# Sheet1.net
KiCad netlist of a schematic drawn in Altium Designer
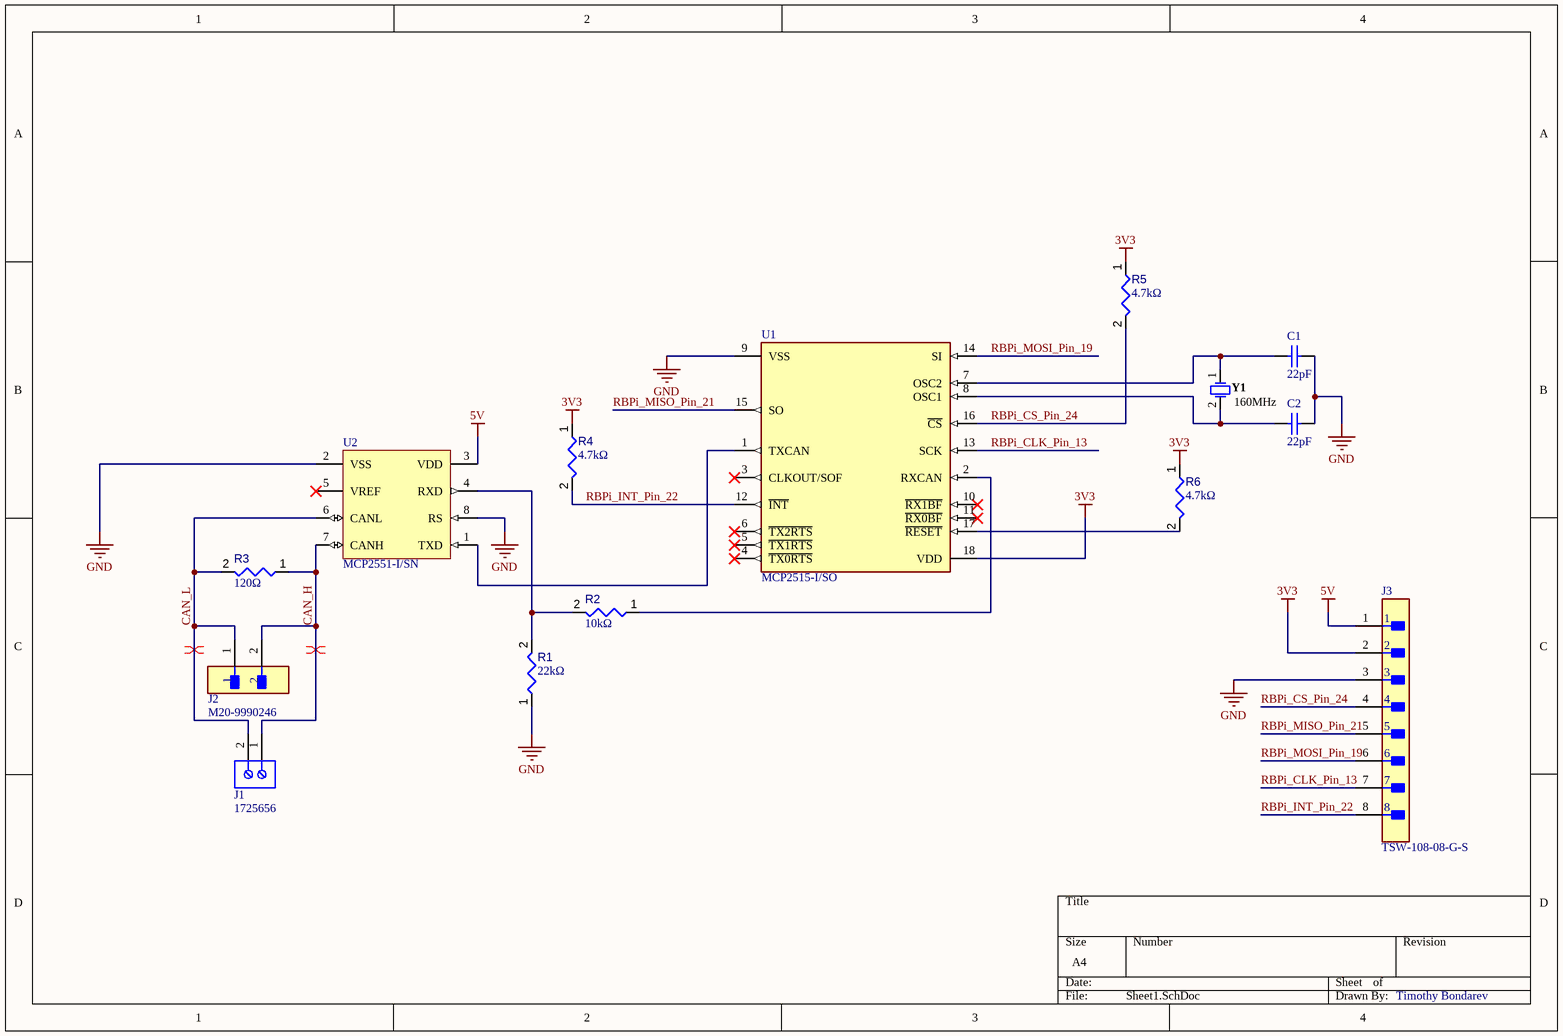
[diagram p0: Sheet1.SchDoc]

(export (version "E")
  (design (tool "Eeschema 10.0.6"))
  (components
    (comp (ref "C1")
      (value "22pF")
      (footprint "CAPC2013X140X50LL20T25")
      (description "Chip Capacitor, 2.2 uF, +/- 10%, 10 V, -55 to 85 degC, 0805 (2012 Metric), RoHS, Tape and Reel")
      (fields (field (name "MANUFACTURER") "AVX"))
      (libsource (lib "Altium Content Vault") (part "CAP-NP-2"))
    )
    (comp (ref "C2")
      (value "22pF")
      (footprint "CAPC2013X140X50LL20T25")
      (description "Chip Capacitor, 2.2 uF, +/- 10%, 10 V, -55 to 85 degC, 0805 (2012 Metric), RoHS, Tape and Reel")
      (fields (field (name "MANUFACTURER") "AVX"))
      (libsource (lib "Altium Content Vault") (part "CAP-NP-2"))
    )
    (comp (ref "J1")
      (value "1725656")
      (footprint "PHOE-1725656-2")
      (description "Male Header, Pitch 2.54 mm, 1 x 2 Position, Height 9 mm, Tail Length 3.5 mm")
      (fields (field (name "MANUFACTURER") "Phoenix Contact"))
      (libsource (lib "Altium Content Vault") (part "CN-1P-F-TB2"))
    )
    (comp (ref "J2")
      (value "M20-9990246")
      (footprint "FP-M20-9990246-MFG")
      (description "CONN HEADER VERT 2POS 2.54MM")
      (fields
        (field (name "OCTOPART") "https://octopart.com/m20-9990246-harwin-2590635")
        (field (name "MANUFACTURER") "Harwin")
      )
      (libsource (lib "Altium Content Vault") (part "3bc925449376181038e59eaffc5286c"))
    )
    (comp (ref "J3")
      (value "TSW-108-08-G-S")
      (footprint "FP-TSW-108-08-G-S-MFG")
      (description "CONN HEADER VERT 8POS 2.54MM")
      (fields
        (field (name "MANUFACTURER") "Samtec")
        (field (name "OCTOPART") "https://octopart.com/tsw-108-08-g-s-samtec-272653")
      )
      (libsource (lib "Altium Content Vault") (part "99ec2b232beb5d2356d4d77f6a047f0"))
    )
    (comp (ref "R1")
      (value "22kΩ")
      (footprint "RESC0805(2012)_L")
      (description "1K 0.125W 5% 0805 (2012 Metric)  SMD")
      (fields (field (name "POWER") "0.125W") (field (name "TOLERANCE") "5%"))
      (libsource (lib "Relectric Car Team") (part "1KR5J"))
    )
    (comp (ref "R2")
      (value "10kΩ")
      (footprint "RESC0805(2012)_L")
      (description "1K 0.125W 5% 0805 (2012 Metric)  SMD")
      (fields (field (name "POWER") "0.125W") (field (name "TOLERANCE") "5%"))
      (libsource (lib "Relectric Car Team") (part "1KR5J"))
    )
    (comp (ref "R3")
      (value "120Ω")
      (footprint "RESC0805(2012)_L")
      (description "1K 0.125W 5% 0805 (2012 Metric)  SMD")
      (fields (field (name "POWER") "0.125W") (field (name "TOLERANCE") "5%"))
      (libsource (lib "Relectric Car Team") (part "1KR5J"))
    )
    (comp (ref "R4")
      (value "4.7kΩ")
      (footprint "RESC0805(2012)_L")
      (description "1K 0.125W 5% 0805 (2012 Metric)  SMD")
      (fields (field (name "POWER") "0.125W") (field (name "TOLERANCE") "5%"))
      (libsource (lib "Relectric Car Team") (part "1KR5J"))
    )
    (comp (ref "R5")
      (value "4.7kΩ")
      (footprint "RESC0805(2012)_L")
      (description "1K 0.125W 5% 0805 (2012 Metric)  SMD")
      (fields (field (name "POWER") "0.125W") (field (name "TOLERANCE") "5%"))
      (libsource (lib "Relectric Car Team") (part "1KR5J"))
    )
    (comp (ref "R6")
      (value "4.7kΩ")
      (footprint "RESC0805(2012)_L")
      (description "1K 0.125W 5% 0805 (2012 Metric)  SMD")
      (fields (field (name "POWER") "0.125W") (field (name "TOLERANCE") "5%"))
      (libsource (lib "Relectric Car Team") (part "1KR5J"))
    )
    (comp (ref "U1")
      (value "MCP2515-I/SO")
      (footprint "FP-C04-051-MFG")
      (description "IC CAN CONTROLLER W/SPI 18SOIC")
      (fields
        (field (name "MANUFACTURER") "Microchip")
        (field (name "OCTOPART") "https://octopart.com/mcp2515-i%2Fso-microchip-430187")
      )
      (libsource (lib "Altium Content Vault") (part "1c78ea6ff576bac94664e2637e1b479"))
    )
    (comp (ref "U2")
      (value "MCP2551-I/SN")
      (footprint "MCHP-SN8_V")
      (fields (field (name "MANUFACTURER") "Microchip"))
      (libsource (lib "Altium Content Vault") (part "MCHP-MCP2551-SN8"))
    )
    (comp (ref "Y1")
      (value "160MHz")
      (footprint "FOX-FOXSLF-2_V")
      (description "Resistance Weld Thru-Hole Crystal, 12 MHz, +/-30 ppm, -20 to 70 degC, 2-Pin THD, RoHS, Bulk")
      (libsource (lib "Altium Content Vault") (part "XTAL-1-2-2"))
    )
  )
  (nets
    (net (code "1") (name "/CAN_H") (class "Default")
      (node (ref "J1") (pin "1") (pinfunction "1_1") (pintype "passive"))
      (node (ref "J2") (pin "2") (pinfunction "2_2") (pintype "passive"))
      (node (ref "R3") (pin "1") (pinfunction "1_1") (pintype "passive"))
      (node (ref "U2") (pin "7") (pinfunction "CANH_7") (pintype "bidirectional"))
    )
    (net (code "2") (name "/CAN_L") (class "Default")
      (node (ref "J1") (pin "2") (pinfunction "2_2") (pintype "passive"))
      (node (ref "J2") (pin "1") (pinfunction "1_1") (pintype "passive"))
      (node (ref "R3") (pin "2") (pinfunction "2_2") (pintype "passive"))
      (node (ref "U2") (pin "6") (pinfunction "CANL_6") (pintype "bidirectional"))
    )
    (net (code "3") (name "/RBPi_CLK_Pin_13") (class "Default")
      (node (ref "J3") (pin "7") (pinfunction "7_7") (pintype "passive"))
      (node (ref "U1") (pin "13") (pinfunction "SCK_13") (pintype "input"))
    )
    (net (code "4") (name "/RBPi_CS_Pin_24") (class "Default")
      (node (ref "J3") (pin "4") (pinfunction "4_4") (pintype "passive"))
      (node (ref "R5") (pin "2") (pinfunction "2_2") (pintype "passive"))
      (node (ref "U1") (pin "16") (pinfunction "~{CS}_16") (pintype "input"))
    )
    (net (code "5") (name "/RBPi_INT_Pin_22") (class "Default")
      (node (ref "J3") (pin "8") (pinfunction "8_8") (pintype "passive"))
      (node (ref "R4") (pin "2") (pinfunction "2_2") (pintype "passive"))
      (node (ref "U1") (pin "12") (pinfunction "~{INT}_12") (pintype "output"))
    )
    (net (code "6") (name "/RBPi_MISO_Pin_21") (class "Default")
      (node (ref "J3") (pin "5") (pinfunction "5_5") (pintype "passive"))
      (node (ref "U1") (pin "15") (pinfunction "SO_15") (pintype "output"))
    )
    (net (code "7") (name "/RBPi_MOSI_Pin_19") (class "Default")
      (node (ref "J3") (pin "6") (pinfunction "6_6") (pintype "passive"))
      (node (ref "U1") (pin "14") (pinfunction "SI_14") (pintype "input"))
    )
    (net (code "8") (name "3V3") (class "Default")
      (node (ref "J3") (pin "2") (pinfunction "2_2") (pintype "passive"))
      (node (ref "R4") (pin "1") (pinfunction "1_1") (pintype "passive"))
      (node (ref "R5") (pin "1") (pinfunction "1_1") (pintype "passive"))
      (node (ref "R6") (pin "1") (pinfunction "1_1") (pintype "passive"))
      (node (ref "U1") (pin "18") (pinfunction "VDD_18") (pintype "power_in"))
    )
    (net (code "9") (name "5V") (class "Default")
      (node (ref "J3") (pin "1") (pinfunction "1_1") (pintype "passive"))
      (node (ref "U2") (pin "3") (pinfunction "VDD_3") (pintype "power_in"))
    )
    (net (code "10") (name "GND") (class "Default")
      (node (ref "C1") (pin "1") (pinfunction "1_1") (pintype "passive"))
      (node (ref "C2") (pin "1") (pinfunction "1_1") (pintype "passive"))
      (node (ref "J3") (pin "3") (pinfunction "3_3") (pintype "passive"))
      (node (ref "R1") (pin "1") (pinfunction "1_1") (pintype "passive"))
      (node (ref "U1") (pin "9") (pinfunction "VSS_9") (pintype "power_in"))
      (node (ref "U2") (pin "2") (pinfunction "VSS_2") (pintype "power_in"))
      (node (ref "U2") (pin "8") (pinfunction "RS_8") (pintype "input"))
    )
    (net (code "11") (name "Net-(U1-OSC1)") (class "Default")
      (node (ref "C2") (pin "2") (pinfunction "2_2") (pintype "passive"))
      (node (ref "U1") (pin "8") (pinfunction "OSC1_8") (pintype "input"))
      (node (ref "Y1") (pin "2") (pinfunction "2_2") (pintype "passive"))
    )
    (net (code "12") (name "Net-(U1-OSC2)") (class "Default")
      (node (ref "C1") (pin "2") (pinfunction "2_2") (pintype "passive"))
      (node (ref "U1") (pin "7") (pinfunction "OSC2_7") (pintype "input"))
      (node (ref "Y1") (pin "1") (pinfunction "1_1") (pintype "passive"))
    )
    (net (code "13") (name "Net-(U1-RXCAN)") (class "Default")
      (node (ref "R2") (pin "1") (pinfunction "1_1") (pintype "passive"))
      (node (ref "U1") (pin "2") (pinfunction "RXCAN_2") (pintype "input"))
    )
    (net (code "14") (name "Net-(U1-TXCAN)") (class "Default")
      (node (ref "U1") (pin "1") (pinfunction "TXCAN_1") (pintype "output"))
      (node (ref "U2") (pin "1") (pinfunction "TXD_1") (pintype "input"))
    )
    (net (code "15") (name "Net-(U1-~{RESET})") (class "Default")
      (node (ref "R6") (pin "2") (pinfunction "2_2") (pintype "passive"))
      (node (ref "U1") (pin "17") (pinfunction "~{RESET}_17") (pintype "input"))
    )
    (net (code "16") (name "Net-(U2-RXD)") (class "Default")
      (node (ref "R1") (pin "2") (pinfunction "2_2") (pintype "passive"))
      (node (ref "R2") (pin "2") (pinfunction "2_2") (pintype "passive"))
      (node (ref "U2") (pin "4") (pinfunction "RXD_4") (pintype "output"))
    )
    (net (code "17") (name "unconnected-(U1-CLKOUT{slash}SOF-Pad3)") (class "Default")
      (node (ref "U1") (pin "3") (pinfunction "CLKOUT/SOF_3") (pintype "output+no_connect"))
    )
    (net (code "18") (name "unconnected-(U1-~{RX0BF}-Pad11)") (class "Default")
      (node (ref "U1") (pin "11") (pinfunction "~{RX0BF}_11") (pintype "input+no_connect"))
    )
    (net (code "19") (name "unconnected-(U1-~{RX1BF}-Pad10)") (class "Default")
      (node (ref "U1") (pin "10") (pinfunction "~{RX1BF}_10") (pintype "input+no_connect"))
    )
    (net (code "20") (name "unconnected-(U1-~{TX0RTS}-Pad4)") (class "Default")
      (node (ref "U1") (pin "4") (pinfunction "~{TX0RTS}_4") (pintype "output+no_connect"))
    )
    (net (code "21") (name "unconnected-(U1-~{TX1RTS}-Pad5)") (class "Default")
      (node (ref "U1") (pin "5") (pinfunction "~{TX1RTS}_5") (pintype "output+no_connect"))
    )
    (net (code "22") (name "unconnected-(U1-~{TX2RTS}-Pad6)") (class "Default")
      (node (ref "U1") (pin "6") (pinfunction "~{TX2RTS}_6") (pintype "output+no_connect"))
    )
    (net (code "23") (name "unconnected-(U2-VREF-Pad5)") (class "Default")
      (node (ref "U2") (pin "5") (pinfunction "VREF_5") (pintype "power_in+no_connect"))
    )
  )
)
